# Scheme.net
KiCad netlist of a schematic drawn in Altium Designer
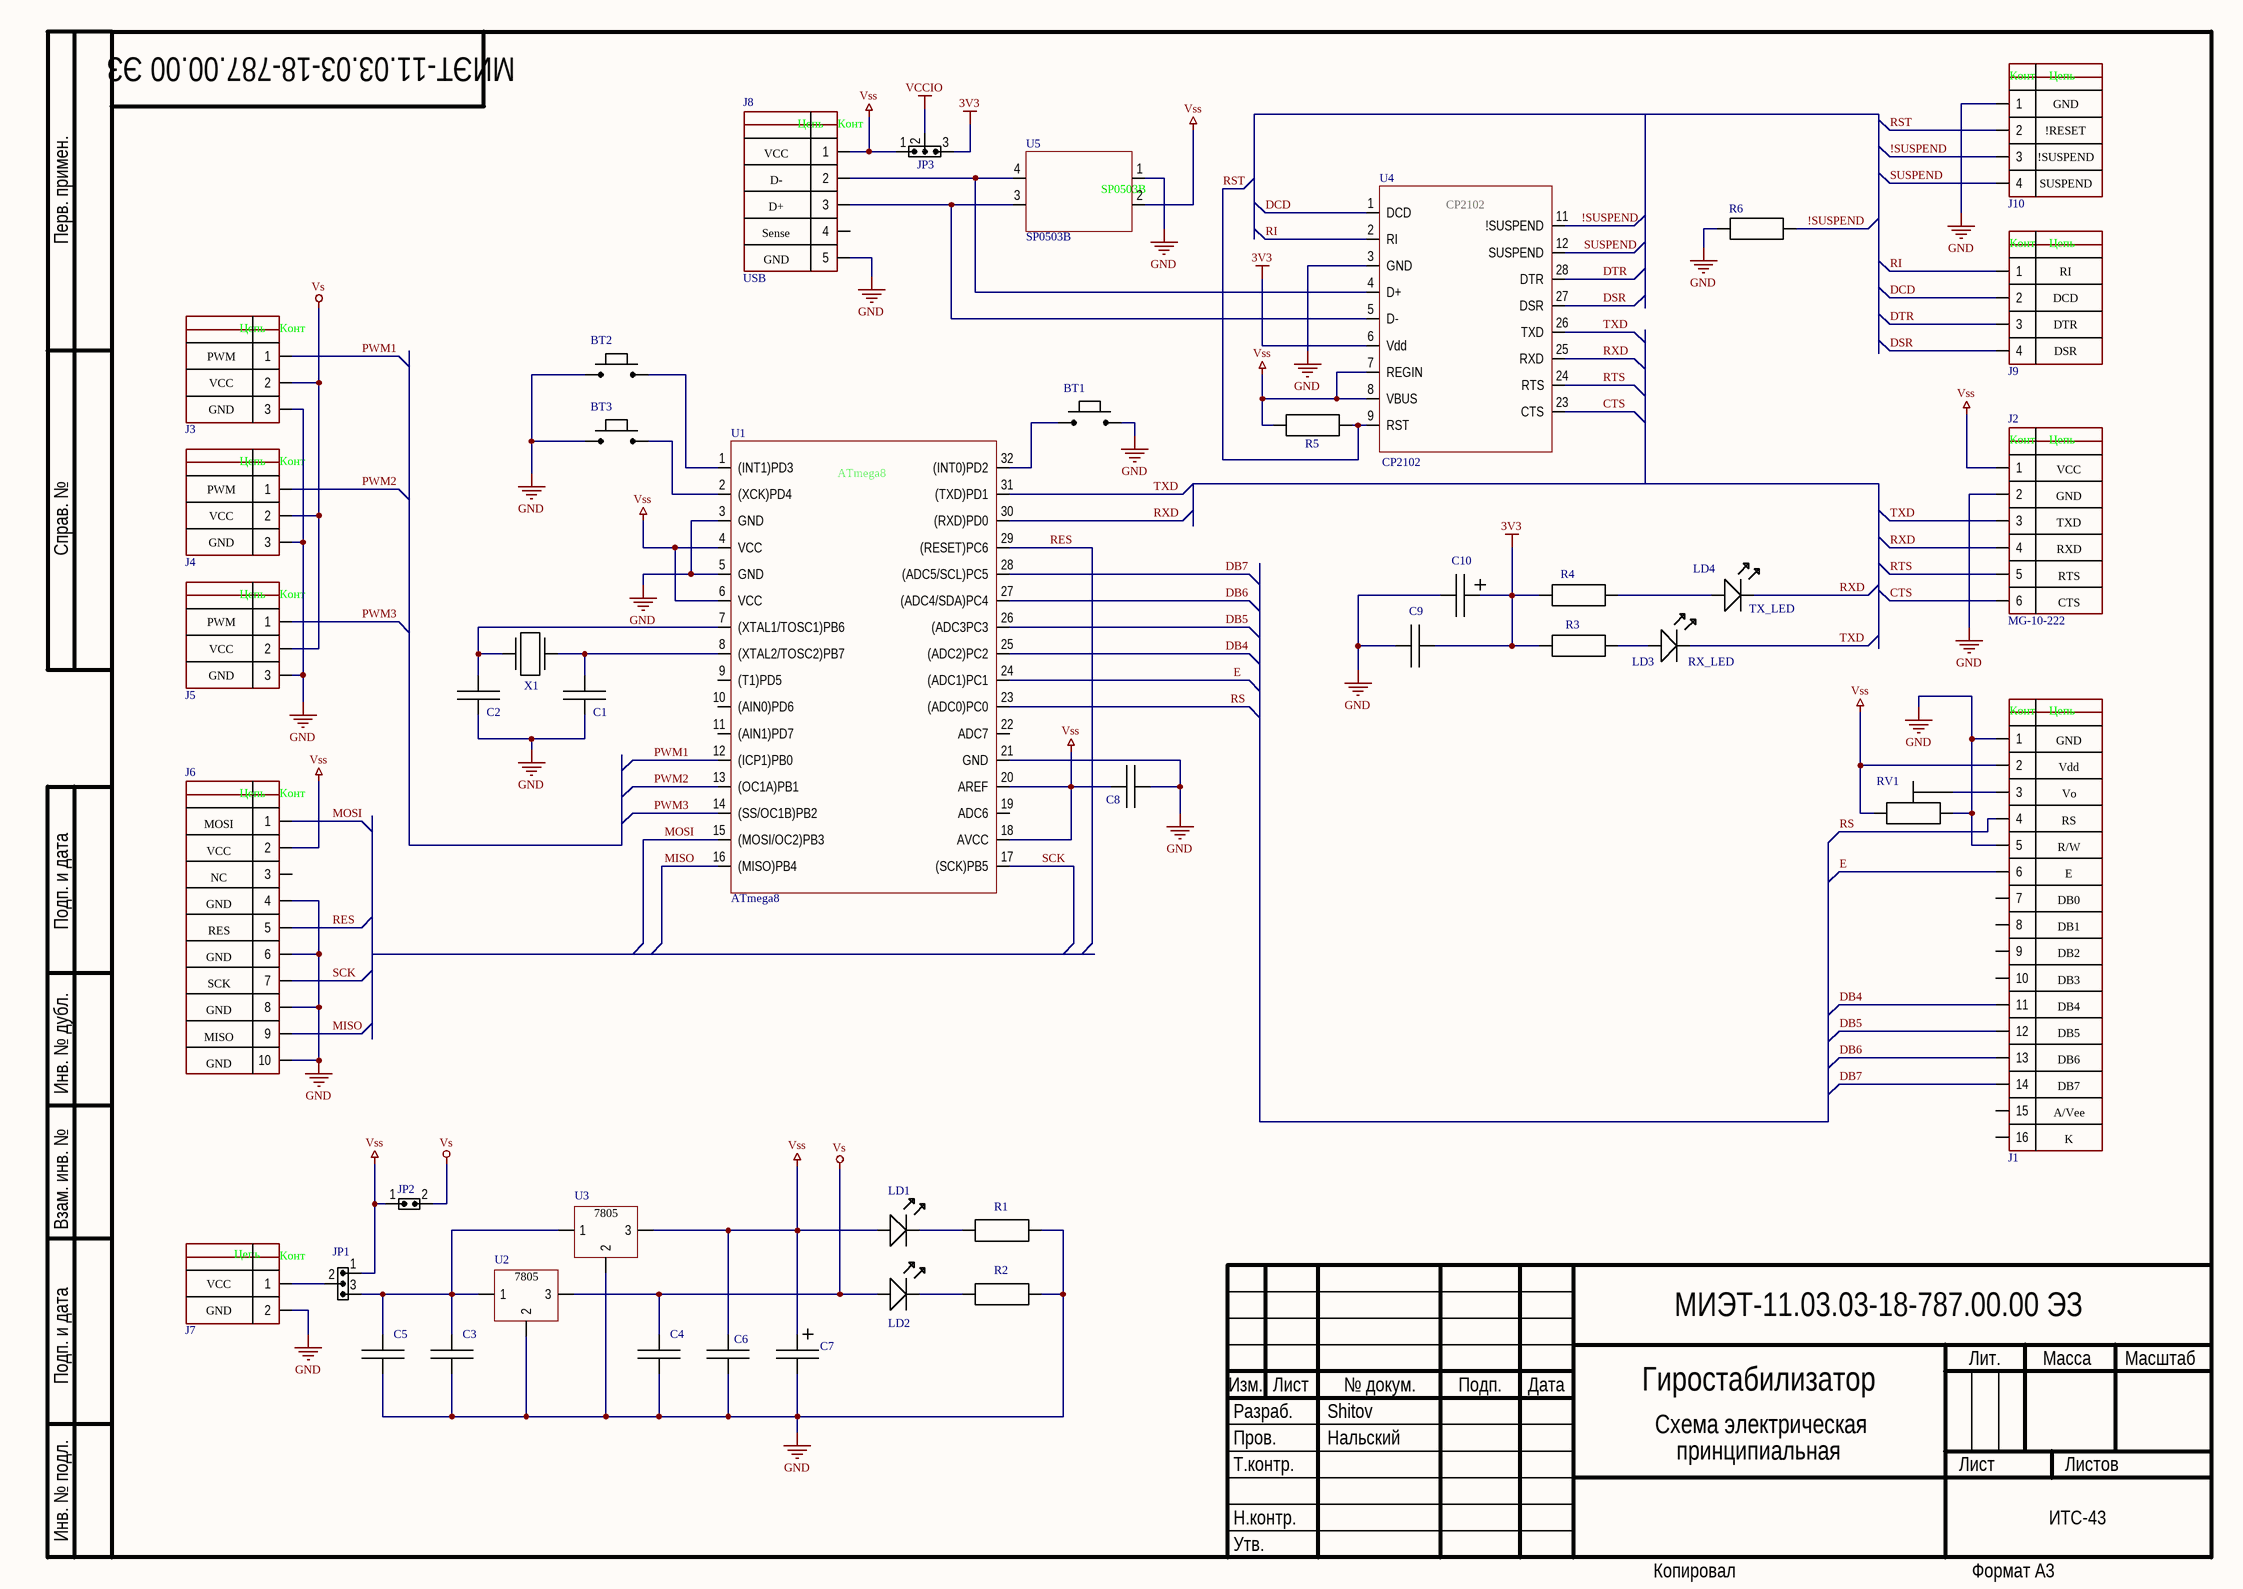
[diagram p0: Scheme.SchDoc]

(export (version "E")
  (design (tool "Eeschema 10.0.6"))
  (components
    (comp (ref "BT1")
      (value "Button")
      (footprint "Button 5x5")
      (libsource (lib "giro-stable") (part "Button"))
    )
    (comp (ref "BT2")
      (value "Button")
      (footprint "Button 5x5")
      (libsource (lib "giro-stable") (part "Button"))
    )
    (comp (ref "BT3")
      (value "Button")
      (footprint "Button 5x5")
      (libsource (lib "giro-stable") (part "Button"))
    )
    (comp (ref "C1") (value "С0805") (footprint "0805") (libsource (lib "giro-stable") (part "С0805")))
    (comp (ref "C2") (value "С0805") (footprint "0805") (libsource (lib "giro-stable") (part "С0805")))
    (comp (ref "C3") (value "С0805") (footprint "0805") (libsource (lib "giro-stable") (part "С0805")))
    (comp (ref "C4") (value "С0805") (footprint "0805") (libsource (lib "giro-stable") (part "С0805")))
    (comp (ref "C5") (value "С0805") (footprint "0805") (libsource (lib "giro-stable") (part "С0805")))
    (comp (ref "C6") (value "С0805") (footprint "0805") (libsource (lib "giro-stable") (part "С0805")))
    (comp (ref "C7") (value "С3/4") (footprint "gyro-stable:A") (libsource (lib "giro-stable") (part "С3/4")))
    (comp (ref "C8") (value "С0805") (footprint "0805") (libsource (lib "giro-stable") (part "С0805")))
    (comp (ref "C9") (value "С0805") (footprint "0805") (libsource (lib "giro-stable") (part "С0805")))
    (comp (ref "C10")
      (value "С3/4")
      (footprint "gyro-stable:A")
      (libsource (lib "giro-stable") (part "С3/4"))
    )
    (comp (ref "J1") (value "LCD") (footprint "LCD") (libsource (lib "giro-stable") (part "LCD")))
    (comp (ref "J2")
      (value "MG-10-222")
      (footprint "DS1022 1x6")
      (libsource (lib "giro-stable") (part "MG-10-222"))
    )
    (comp (ref "J3") (value "Servo") (footprint "DS1022 1x3") (libsource (lib "giro-stable") (part "Servo")))
    (comp (ref "J4") (value "Servo") (footprint "DS1022 1x3") (libsource (lib "giro-stable") (part "Servo")))
    (comp (ref "J5") (value "Servo") (footprint "DS1022 1x3") (libsource (lib "giro-stable") (part "Servo")))
    (comp (ref "J6")
      (value "Вилка ВН-10")
      (footprint "Вилка ВН-10")
      (libsource (lib "giro-stable") (part "Вилка ВН-10"))
    )
    (comp (ref "J7")
      (value "Input power")
      (footprint "Input power")
      (libsource (lib "giro-stable") (part "Input power"))
    )
    (comp (ref "J8") (value "USB") (footprint "micro-USB") (libsource (lib "giro-stable") (part "USB")))
    (comp (ref "J9")
      (value "Other header")
      (footprint "Other header")
      (libsource (lib "giro-stable") (part "Other header"))
    )
    (comp (ref "J10")
      (value "Other header 2")
      (footprint "Other header")
      (libsource (lib "giro-stable") (part "Other header 2"))
    )
    (comp (ref "JP1") (value "Jumper 3") (footprint "JUMPER 3") (libsource (lib "") (part "Jumper 3_1")))
    (comp (ref "JP2") (value "Jumper") (footprint "Jumper") (libsource (lib "giro-stable") (part "Jumper")))
    (comp (ref "JP3")
      (value "Jumper 3")
      (footprint "JUMPER 3")
      (libsource (lib "giro-stable") (part "Jumper 3"))
    )
    (comp (ref "LD1") (value "LED") (footprint "LED") (libsource (lib "giro-stable") (part "LED")))
    (comp (ref "LD2") (value "LED") (footprint "LED") (libsource (lib "giro-stable") (part "LED")))
    (comp (ref "LD3") (value "RX_LED") (footprint "LED") (libsource (lib "giro-stable") (part "LED")))
    (comp (ref "LD4") (value "TX_LED") (footprint "LED") (libsource (lib "giro-stable") (part "LED")))
    (comp (ref "R1") (value "R0805") (footprint "0805") (libsource (lib "giro-stable") (part "R0805")))
    (comp (ref "R2") (value "R0805") (footprint "0805") (libsource (lib "giro-stable") (part "R0805")))
    (comp (ref "R3") (value "R0805") (footprint "0805") (libsource (lib "giro-stable") (part "R0805")))
    (comp (ref "R4") (value "R0805") (footprint "0805") (libsource (lib "giro-stable") (part "R0805")))
    (comp (ref "R5") (value "R0805") (footprint "0805") (libsource (lib "") (part "R0805_1")))
    (comp (ref "R6") (value "R0805") (footprint "0805") (libsource (lib "giro-stable") (part "R0805")))
    (comp (ref "RV1") (value "POT") (footprint "POT") (libsource (lib "giro-stable") (part "POT")))
    (comp (ref "U1") (value "ATmega8") (footprint "ATmega8") (libsource (lib "giro-stable") (part "ATmega8")))
    (comp (ref "U2")
      (value "7805 SMD")
      (footprint "7805 SMD")
      (libsource (lib "giro-stable") (part "7805 SMD"))
    )
    (comp (ref "U3")
      (value "7805 SMD")
      (footprint "7805 SMD")
      (libsource (lib "giro-stable") (part "7805 SMD"))
    )
    (comp (ref "U4") (value "CP2102") (footprint "CP2102") (libsource (lib "giro-stable") (part "CP2102")))
    (comp (ref "U5")
      (value "SP0503B")
      (footprint "SP0503B")
      (description "TO-253")
      (libsource (lib "giro-stable") (part "SP0503B"))
    )
    (comp (ref "X1") (value "XTAL") (footprint "HC-49SM") (libsource (lib "giro-stable") (part "XTAL")))
  )
  (nets
    (net (code "1") (name "/!SUSPEND") (class "Default")
      (node (ref "J10") (pin "3") (pinfunction "3_3") (pintype "passive"))
      (node (ref "R6") (pin "2") (pinfunction "2_2") (pintype "passive"))
      (node (ref "U4") (pin "11") (pinfunction "!SUSPEND_11") (pintype "passive"))
    )
    (net (code "2") (name "/CTS") (class "Default")
      (node (ref "J2") (pin "6") (pinfunction "6_6") (pintype "passive"))
      (node (ref "U4") (pin "23") (pinfunction "CTS_23") (pintype "passive"))
    )
    (net (code "3") (name "/DB4") (class "Default")
      (node (ref "J1") (pin "11") (pinfunction "11_11") (pintype "passive"))
      (node (ref "U1") (pin "25") (pinfunction "(ADC2)PC2_25") (pintype "passive"))
    )
    (net (code "4") (name "/DB5") (class "Default")
      (node (ref "J1") (pin "12") (pinfunction "12_12") (pintype "passive"))
      (node (ref "U1") (pin "26") (pinfunction "(ADC3PC3_26") (pintype "passive"))
    )
    (net (code "5") (name "/DB6") (class "Default")
      (node (ref "J1") (pin "13") (pinfunction "13_13") (pintype "passive"))
      (node (ref "U1") (pin "27") (pinfunction "(ADC4/SDA)PC4_27") (pintype "passive"))
    )
    (net (code "6") (name "/DB7") (class "Default")
      (node (ref "J1") (pin "14") (pinfunction "14_14") (pintype "passive"))
      (node (ref "U1") (pin "28") (pinfunction "(ADC5/SCL)PC5_28") (pintype "passive"))
    )
    (net (code "7") (name "/DCD") (class "Default")
      (node (ref "J9") (pin "2") (pinfunction "2_2") (pintype "passive"))
      (node (ref "U4") (pin "1") (pinfunction "DCD_1") (pintype "passive"))
    )
    (net (code "8") (name "/DSR") (class "Default")
      (node (ref "J9") (pin "4") (pinfunction "4_4") (pintype "passive"))
      (node (ref "U4") (pin "27") (pinfunction "DSR_27") (pintype "passive"))
    )
    (net (code "9") (name "/DTR") (class "Default")
      (node (ref "J9") (pin "3") (pinfunction "3_3") (pintype "passive"))
      (node (ref "U4") (pin "28") (pinfunction "DTR_28") (pintype "passive"))
    )
    (net (code "10") (name "/E") (class "Default")
      (node (ref "J1") (pin "6") (pinfunction "6_6") (pintype "passive"))
      (node (ref "U1") (pin "24") (pinfunction "(ADC1)PC1_24") (pintype "passive"))
    )
    (net (code "11") (name "/MISO") (class "Default")
      (node (ref "J6") (pin "9") (pinfunction "9_9") (pintype "passive"))
      (node (ref "U1") (pin "16") (pinfunction "(MISO)PB4_16") (pintype "passive"))
    )
    (net (code "12") (name "/MOSI") (class "Default")
      (node (ref "J6") (pin "1") (pinfunction "1_1") (pintype "passive"))
      (node (ref "U1") (pin "15") (pinfunction "(MOSI/OC2)PB3_15") (pintype "passive"))
    )
    (net (code "13") (name "/PWM1") (class "Default")
      (node (ref "J3") (pin "1") (pinfunction "1_1") (pintype "passive"))
      (node (ref "U1") (pin "12") (pinfunction "(ICP1)PB0_12") (pintype "passive"))
    )
    (net (code "14") (name "/PWM2") (class "Default")
      (node (ref "J4") (pin "1") (pinfunction "1_1") (pintype "passive"))
      (node (ref "U1") (pin "13") (pinfunction "(OC1A)PB1_13") (pintype "passive"))
    )
    (net (code "15") (name "/PWM3") (class "Default")
      (node (ref "J5") (pin "1") (pinfunction "1_1") (pintype "passive"))
      (node (ref "U1") (pin "14") (pinfunction "(SS/OC1B)PB2_14") (pintype "passive"))
    )
    (net (code "16") (name "/RES") (class "Default")
      (node (ref "J6") (pin "5") (pinfunction "5_5") (pintype "passive"))
      (node (ref "U1") (pin "29") (pinfunction "(RESET)PC6_29") (pintype "passive"))
    )
    (net (code "17") (name "/RI") (class "Default")
      (node (ref "J9") (pin "1") (pinfunction "1_1") (pintype "passive"))
      (node (ref "U4") (pin "2") (pinfunction "RI_2") (pintype "passive"))
    )
    (net (code "18") (name "/RS") (class "Default")
      (node (ref "J1") (pin "4") (pinfunction "4_4") (pintype "passive"))
      (node (ref "U1") (pin "23") (pinfunction "(ADC0)PC0_23") (pintype "passive"))
    )
    (net (code "19") (name "/RST") (class "Default")
      (node (ref "J10") (pin "2") (pinfunction "2_2") (pintype "passive"))
      (node (ref "R5") (pin "2") (pinfunction "2_2") (pintype "passive"))
      (node (ref "U4") (pin "9") (pinfunction "RST_9") (pintype "passive"))
    )
    (net (code "20") (name "/RTS") (class "Default")
      (node (ref "J2") (pin "5") (pinfunction "5_5") (pintype "passive"))
      (node (ref "U4") (pin "24") (pinfunction "RTS_24") (pintype "passive"))
    )
    (net (code "21") (name "/RXD") (class "Default")
      (node (ref "J2") (pin "4") (pinfunction "4_4") (pintype "passive"))
      (node (ref "LD4") (pin "2") (pintype "passive"))
      (node (ref "U1") (pin "30") (pinfunction "(RXD)PD0_30") (pintype "passive"))
      (node (ref "U4") (pin "25") (pinfunction "RXD_25") (pintype "passive"))
    )
    (net (code "22") (name "/SCK") (class "Default")
      (node (ref "J6") (pin "7") (pinfunction "7_7") (pintype "passive"))
      (node (ref "U1") (pin "17") (pinfunction "(SCK)PB5_17") (pintype "passive"))
    )
    (net (code "23") (name "/SUSPEND") (class "Default")
      (node (ref "J10") (pin "4") (pinfunction "4_4") (pintype "passive"))
      (node (ref "U4") (pin "12") (pinfunction "SUSPEND_12") (pintype "passive"))
    )
    (net (code "24") (name "/TXD") (class "Default")
      (node (ref "J2") (pin "3") (pinfunction "3_3") (pintype "passive"))
      (node (ref "LD3") (pin "2") (pintype "passive"))
      (node (ref "U1") (pin "31") (pinfunction "(TXD)PD1_31") (pintype "passive"))
      (node (ref "U4") (pin "26") (pinfunction "TXD_26") (pintype "passive"))
    )
    (net (code "25") (name "3V3") (class "Default")
      (node (ref "C10") (pin "1") (pinfunction "1_1") (pintype "passive"))
      (node (ref "C9") (pin "2") (pinfunction "2_2") (pintype "passive"))
      (node (ref "JP3") (pin "3") (pintype "passive"))
      (node (ref "R3") (pin "1") (pinfunction "1_1") (pintype "passive"))
      (node (ref "R4") (pin "1") (pinfunction "1_1") (pintype "passive"))
      (node (ref "U4") (pin "6") (pinfunction "Vdd_6") (pintype "passive"))
    )
    (net (code "26") (name "GND") (class "Default")
      (node (ref "BT1") (pin "2") (pintype "passive"))
      (node (ref "BT2") (pin "1") (pintype "passive"))
      (node (ref "BT3") (pin "1") (pintype "passive"))
      (node (ref "C1") (pin "1") (pinfunction "1_1") (pintype "passive"))
      (node (ref "C10") (pin "2") (pinfunction "2_2") (pintype "passive"))
      (node (ref "C2") (pin "1") (pinfunction "1_1") (pintype "passive"))
      (node (ref "C3") (pin "1") (pinfunction "1_1") (pintype "passive"))
      (node (ref "C4") (pin "1") (pinfunction "1_1") (pintype "passive"))
      (node (ref "C5") (pin "1") (pinfunction "1_1") (pintype "passive"))
      (node (ref "C6") (pin "1") (pinfunction "1_1") (pintype "passive"))
      (node (ref "C7") (pin "2") (pinfunction "2_2") (pintype "passive"))
      (node (ref "C8") (pin "2") (pinfunction "2_2") (pintype "passive"))
      (node (ref "C9") (pin "1") (pinfunction "1_1") (pintype "passive"))
      (node (ref "J1") (pin "1") (pinfunction "1_1") (pintype "passive"))
      (node (ref "J1") (pin "5") (pinfunction "5_5") (pintype "passive"))
      (node (ref "J10") (pin "1") (pinfunction "1_1") (pintype "passive"))
      (node (ref "J2") (pin "2") (pinfunction "2_2") (pintype "passive"))
      (node (ref "J3") (pin "3") (pinfunction "3_3") (pintype "passive"))
      (node (ref "J4") (pin "3") (pinfunction "3_3") (pintype "passive"))
      (node (ref "J5") (pin "3") (pinfunction "3_3") (pintype "passive"))
      (node (ref "J6") (pin "10") (pinfunction "10_10") (pintype "passive"))
      (node (ref "J6") (pin "4") (pinfunction "4_4") (pintype "passive"))
      (node (ref "J6") (pin "6") (pinfunction "6_6") (pintype "passive"))
      (node (ref "J6") (pin "8") (pinfunction "8_8") (pintype "passive"))
      (node (ref "J7") (pin "2") (pinfunction "2_2") (pintype "passive"))
      (node (ref "J8") (pin "5") (pinfunction "5_5") (pintype "passive"))
      (node (ref "R1") (pin "2") (pinfunction "2_2") (pintype "passive"))
      (node (ref "R2") (pin "2") (pinfunction "2_2") (pintype "passive"))
      (node (ref "R6") (pin "1") (pinfunction "1_1") (pintype "passive"))
      (node (ref "RV1") (pin "3") (pinfunction "3_3") (pintype "passive"))
      (node (ref "U1") (pin "21") (pinfunction "GND_21") (pintype "passive"))
      (node (ref "U1") (pin "3") (pinfunction "GND_3") (pintype "passive"))
      (node (ref "U1") (pin "5") (pinfunction "GND_5") (pintype "passive"))
      (node (ref "U2") (pin "2") (pinfunction "2_2") (pintype "passive"))
      (node (ref "U3") (pin "2") (pinfunction "2_2") (pintype "passive"))
      (node (ref "U4") (pin "3") (pinfunction "GND_3") (pintype "passive"))
      (node (ref "U5") (pin "1") (pinfunction "1_1") (pintype "passive"))
    )
    (net (code "27") (name "Net-(C3-Pad2)") (class "Default")
      (node (ref "C3") (pin "2") (pinfunction "2_2") (pintype "passive"))
      (node (ref "C5") (pin "2") (pinfunction "2_2") (pintype "passive"))
      (node (ref "JP1") (pin "3") (pintype "passive"))
      (node (ref "U2") (pin "1") (pinfunction "1_1") (pintype "passive"))
      (node (ref "U3") (pin "1") (pinfunction "1_1") (pintype "passive"))
    )
    (net (code "28") (name "Net-(J1-Pad3)") (class "Default")
      (node (ref "J1") (pin "3") (pinfunction "3_3") (pintype "passive"))
      (node (ref "RV1") (pin "2") (pinfunction "2_2") (pintype "passive"))
    )
    (net (code "29") (name "Net-(J7-Pad1)") (class "Default")
      (node (ref "J7") (pin "1") (pinfunction "1_1") (pintype "passive"))
      (node (ref "JP1") (pin "2") (pintype "passive"))
    )
    (net (code "30") (name "Net-(LD1-Pad2)") (class "Default")
      (node (ref "LD1") (pin "2") (pintype "passive"))
      (node (ref "R1") (pin "1") (pinfunction "1_1") (pintype "passive"))
    )
    (net (code "31") (name "Net-(LD2-Pad2)") (class "Default")
      (node (ref "LD2") (pin "2") (pintype "passive"))
      (node (ref "R2") (pin "1") (pinfunction "1_1") (pintype "passive"))
    )
    (net (code "32") (name "Net-(LD3-Pad1)") (class "Default")
      (node (ref "LD3") (pin "1") (pintype "passive"))
      (node (ref "R3") (pin "2") (pinfunction "2_2") (pintype "passive"))
    )
    (net (code "33") (name "Net-(LD4-Pad1)") (class "Default")
      (node (ref "LD4") (pin "1") (pintype "passive"))
      (node (ref "R4") (pin "2") (pinfunction "2_2") (pintype "passive"))
    )
    (net (code "34") (name "Net-(U1-(INT0)PD2)") (class "Default")
      (node (ref "BT1") (pin "1") (pintype "passive"))
      (node (ref "U1") (pin "32") (pinfunction "(INT0)PD2_32") (pintype "passive"))
    )
    (net (code "35") (name "Net-(U1-(INT1)PD3)") (class "Default")
      (node (ref "BT2") (pin "2") (pintype "passive"))
      (node (ref "U1") (pin "1") (pinfunction "(INT1)PD3_1") (pintype "passive"))
    )
    (net (code "36") (name "Net-(U1-(XCK)PD4)") (class "Default")
      (node (ref "BT3") (pin "2") (pintype "passive"))
      (node (ref "U1") (pin "2") (pinfunction "(XCK)PD4_2") (pintype "passive"))
    )
    (net (code "37") (name "Net-(U1-(XTAL1{slash}TOSC1)PB6)") (class "Default")
      (node (ref "C2") (pin "2") (pinfunction "2_2") (pintype "passive"))
      (node (ref "U1") (pin "7") (pinfunction "(XTAL1/TOSC1)PB6_7") (pintype "passive"))
      (node (ref "X1") (pin "1") (pintype "passive"))
    )
    (net (code "38") (name "Net-(U1-(XTAL2{slash}TOSC2)PB7)") (class "Default")
      (node (ref "C1") (pin "2") (pinfunction "2_2") (pintype "passive"))
      (node (ref "U1") (pin "8") (pinfunction "(XTAL2/TOSC2)PB7_8") (pintype "passive"))
      (node (ref "X1") (pin "2") (pintype "passive"))
    )
    (net (code "39") (name "Net-(U4-D+)") (class "Default")
      (node (ref "J8") (pin "2") (pinfunction "2_2") (pintype "passive"))
      (node (ref "U4") (pin "4") (pinfunction "D+_4") (pintype "passive"))
      (node (ref "U5") (pin "4") (pinfunction "4_4") (pintype "passive"))
    )
    (net (code "40") (name "Net-(U4-D-)") (class "Default")
      (node (ref "J8") (pin "3") (pinfunction "3_3") (pintype "passive"))
      (node (ref "U4") (pin "5") (pinfunction "D-_5") (pintype "passive"))
      (node (ref "U5") (pin "3") (pinfunction "3_3") (pintype "passive"))
    )
    (net (code "41") (name "VCCIO") (class "Default") (node (ref "JP3") (pin "2") (pintype "passive")))
    (net (code "42") (name "Vs") (class "Default")
      (node (ref "C4") (pin "2") (pinfunction "2_2") (pintype "passive"))
      (node (ref "J3") (pin "2") (pinfunction "2_2") (pintype "passive"))
      (node (ref "J4") (pin "2") (pinfunction "2_2") (pintype "passive"))
      (node (ref "J5") (pin "2") (pinfunction "2_2") (pintype "passive"))
      (node (ref "JP2") (pin "2") (pintype "passive"))
      (node (ref "LD2") (pin "1") (pintype "passive"))
      (node (ref "U2") (pin "3") (pinfunction "3_3") (pintype "passive"))
    )
    (net (code "43") (name "Vss") (class "Default")
      (node (ref "C6") (pin "2") (pinfunction "2_2") (pintype "passive"))
      (node (ref "C7") (pin "1") (pinfunction "1_1") (pintype "passive"))
      (node (ref "C8") (pin "1") (pinfunction "1_1") (pintype "passive"))
      (node (ref "J1") (pin "2") (pinfunction "2_2") (pintype "passive"))
      (node (ref "J2") (pin "1") (pinfunction "1_1") (pintype "passive"))
      (node (ref "J6") (pin "2") (pinfunction "2_2") (pintype "passive"))
      (node (ref "J8") (pin "1") (pinfunction "1_1") (pintype "passive"))
      (node (ref "JP1") (pin "1") (pintype "passive"))
      (node (ref "JP2") (pin "1") (pintype "passive"))
      (node (ref "JP3") (pin "1") (pintype "passive"))
      (node (ref "LD1") (pin "1") (pintype "passive"))
      (node (ref "R5") (pin "1") (pinfunction "1_1") (pintype "passive"))
      (node (ref "RV1") (pin "1") (pinfunction "1_1") (pintype "passive"))
      (node (ref "U1") (pin "18") (pinfunction "AVCC_18") (pintype "passive"))
      (node (ref "U1") (pin "20") (pinfunction "AREF_20") (pintype "passive"))
      (node (ref "U1") (pin "4") (pinfunction "VCC_4") (pintype "passive"))
      (node (ref "U1") (pin "6") (pinfunction "VCC_6") (pintype "passive"))
      (node (ref "U3") (pin "3") (pinfunction "3_3") (pintype "passive"))
      (node (ref "U4") (pin "7") (pinfunction "REGIN_7") (pintype "passive"))
      (node (ref "U4") (pin "8") (pinfunction "VBUS_8") (pintype "passive"))
      (node (ref "U5") (pin "2") (pinfunction "2_2") (pintype "passive"))
    )
    (net (code "44") (name "unconnected-(J1-Pad7)") (class "Default")
      (node (ref "J1") (pin "7") (pinfunction "7_7") (pintype "passive"))
    )
    (net (code "45") (name "unconnected-(J1-Pad8)") (class "Default")
      (node (ref "J1") (pin "8") (pinfunction "8_8") (pintype "passive"))
    )
    (net (code "46") (name "unconnected-(J1-Pad9)") (class "Default")
      (node (ref "J1") (pin "9") (pinfunction "9_9") (pintype "passive"))
    )
    (net (code "47") (name "unconnected-(J1-Pad10)") (class "Default")
      (node (ref "J1") (pin "10") (pinfunction "10_10") (pintype "passive"))
    )
    (net (code "48") (name "unconnected-(J1-Pad15)") (class "Default")
      (node (ref "J1") (pin "15") (pinfunction "15_15") (pintype "passive"))
    )
    (net (code "49") (name "unconnected-(J1-Pad16)") (class "Default")
      (node (ref "J1") (pin "16") (pinfunction "16_16") (pintype "passive"))
    )
    (net (code "50") (name "unconnected-(J6-Pad3)") (class "Default")
      (node (ref "J6") (pin "3") (pinfunction "3_3") (pintype "passive"))
    )
    (net (code "51") (name "unconnected-(J8-Pad4)") (class "Default")
      (node (ref "J8") (pin "4") (pinfunction "4_4") (pintype "passive"))
    )
    (net (code "52") (name "unconnected-(U1-(AIN0)PD6-Pad10)") (class "Default")
      (node (ref "U1") (pin "10") (pinfunction "(AIN0)PD6_10") (pintype "passive"))
    )
    (net (code "53") (name "unconnected-(U1-(AIN1)PD7-Pad11)") (class "Default")
      (node (ref "U1") (pin "11") (pinfunction "(AIN1)PD7_11") (pintype "passive"))
    )
    (net (code "54") (name "unconnected-(U1-(T1)PD5-Pad9)") (class "Default")
      (node (ref "U1") (pin "9") (pinfunction "(T1)PD5_9") (pintype "passive"))
    )
    (net (code "55") (name "unconnected-(U1-ADC6-Pad19)") (class "Default")
      (node (ref "U1") (pin "19") (pinfunction "ADC6_19") (pintype "passive"))
    )
    (net (code "56") (name "unconnected-(U1-ADC7-Pad22)") (class "Default")
      (node (ref "U1") (pin "22") (pinfunction "ADC7_22") (pintype "passive"))
    )
  )
)
